# hv4layerSWV2.net
KiCad netlist of a schematic drawn in EAGLE
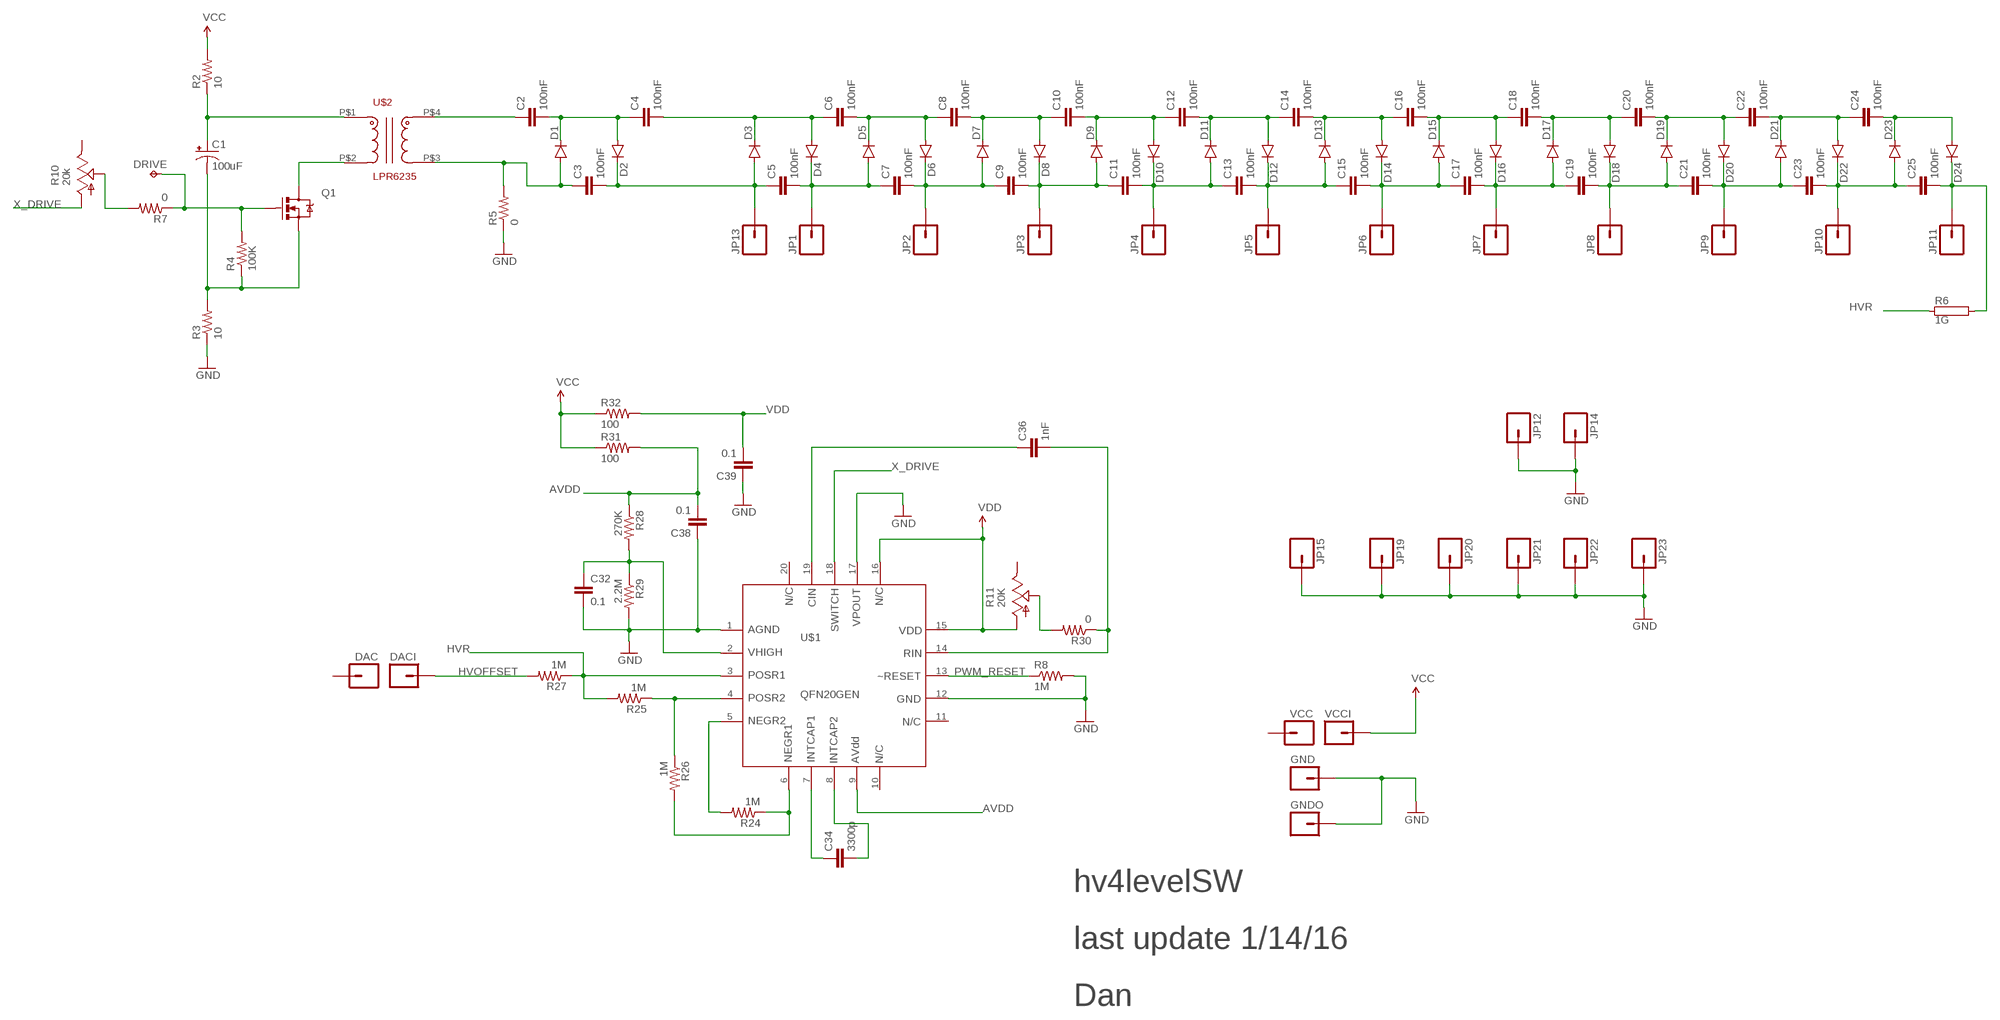
[diagram p0: schematic, sheet 1]

(export (version "E")
  (design (tool "Eeschema 10.0.6"))
  (components
    (comp (ref "C1")
      (value "100uF")
      (footprint "eagle-import:EIA6032")
      (libsource (lib "eagle-import") (part "CAP_POL6032"))
    )
    (comp (ref "C2")
      (value "100nF")
      (footprint "eagle-import:1210")
      (libsource (lib "eagle-import") (part "CAP1210"))
    )
    (comp (ref "C3")
      (value "100nF")
      (footprint "eagle-import:1210")
      (libsource (lib "eagle-import") (part "CAP1210"))
    )
    (comp (ref "C4")
      (value "100nF")
      (footprint "eagle-import:1210")
      (libsource (lib "eagle-import") (part "CAP1210"))
    )
    (comp (ref "C5")
      (value "100nF")
      (footprint "eagle-import:1210")
      (libsource (lib "eagle-import") (part "CAP1210"))
    )
    (comp (ref "C6")
      (value "100nF")
      (footprint "eagle-import:1210")
      (libsource (lib "eagle-import") (part "CAP1210"))
    )
    (comp (ref "C7")
      (value "100nF")
      (footprint "eagle-import:1210")
      (libsource (lib "eagle-import") (part "CAP1210"))
    )
    (comp (ref "C8")
      (value "100nF")
      (footprint "eagle-import:1210")
      (libsource (lib "eagle-import") (part "CAP1210"))
    )
    (comp (ref "C9")
      (value "100nF")
      (footprint "eagle-import:1210")
      (libsource (lib "eagle-import") (part "CAP1210"))
    )
    (comp (ref "C10")
      (value "100nF")
      (footprint "eagle-import:1210")
      (libsource (lib "eagle-import") (part "CAP1210"))
    )
    (comp (ref "C11")
      (value "100nF")
      (footprint "eagle-import:1210")
      (libsource (lib "eagle-import") (part "CAP1210"))
    )
    (comp (ref "C12")
      (value "100nF")
      (footprint "eagle-import:1210")
      (libsource (lib "eagle-import") (part "CAP1210"))
    )
    (comp (ref "C13")
      (value "100nF")
      (footprint "eagle-import:1210")
      (libsource (lib "eagle-import") (part "CAP1210"))
    )
    (comp (ref "C14")
      (value "100nF")
      (footprint "eagle-import:1210")
      (libsource (lib "eagle-import") (part "CAP1210"))
    )
    (comp (ref "C15")
      (value "100nF")
      (footprint "eagle-import:1210")
      (libsource (lib "eagle-import") (part "CAP1210"))
    )
    (comp (ref "C16")
      (value "100nF")
      (footprint "eagle-import:1210")
      (libsource (lib "eagle-import") (part "CAP1210"))
    )
    (comp (ref "C17")
      (value "100nF")
      (footprint "eagle-import:1210")
      (libsource (lib "eagle-import") (part "CAP1210"))
    )
    (comp (ref "C18")
      (value "100nF")
      (footprint "eagle-import:1210")
      (libsource (lib "eagle-import") (part "CAP1210"))
    )
    (comp (ref "C19")
      (value "100nF")
      (footprint "eagle-import:1210")
      (libsource (lib "eagle-import") (part "CAP1210"))
    )
    (comp (ref "C20")
      (value "100nF")
      (footprint "eagle-import:1210")
      (libsource (lib "eagle-import") (part "CAP1210"))
    )
    (comp (ref "C21")
      (value "100nF")
      (footprint "eagle-import:1210")
      (libsource (lib "eagle-import") (part "CAP1210"))
    )
    (comp (ref "C22")
      (value "100nF")
      (footprint "eagle-import:1210")
      (libsource (lib "eagle-import") (part "CAP1210"))
    )
    (comp (ref "C23")
      (value "100nF")
      (footprint "eagle-import:1210")
      (libsource (lib "eagle-import") (part "CAP1210"))
    )
    (comp (ref "C24")
      (value "100nF")
      (footprint "eagle-import:1210")
      (libsource (lib "eagle-import") (part "CAP1210"))
    )
    (comp (ref "C25")
      (value "100nF")
      (footprint "eagle-import:1210")
      (libsource (lib "eagle-import") (part "CAP1210"))
    )
    (comp (ref "C32")
      (value "0.1")
      (footprint "eagle-import:0805")
      (libsource (lib "eagle-import") (part "22UF-6.3V-20%(0805)"))
    )
    (comp (ref "C34")
      (value "3300p")
      (footprint "eagle-import:0805")
      (libsource (lib "eagle-import") (part "22UF-6.3V-20%(0805)"))
    )
    (comp (ref "C36")
      (value "1nF")
      (footprint "eagle-import:0805")
      (libsource (lib "eagle-import") (part "22UF-6.3V-20%(0805)"))
    )
    (comp (ref "C38")
      (value "0.1")
      (footprint "eagle-import:0805")
      (libsource (lib "eagle-import") (part "22UF-6.3V-20%(0805)"))
    )
    (comp (ref "C39")
      (value "0.1")
      (footprint "eagle-import:0805")
      (libsource (lib "eagle-import") (part "22UF-6.3V-20%(0805)"))
    )
    (comp (ref "D1")
      (value "DIODESOT23")
      (footprint "eagle-import:SOT23-3")
      (libsource (lib "eagle-import") (part "DIODESOT23"))
    )
    (comp (ref "D2")
      (value "DIODESOT23")
      (footprint "eagle-import:SOT23-3")
      (libsource (lib "eagle-import") (part "DIODESOT23"))
    )
    (comp (ref "D3")
      (value "DIODESOT23")
      (footprint "eagle-import:SOT23-3")
      (libsource (lib "eagle-import") (part "DIODESOT23"))
    )
    (comp (ref "D4")
      (value "DIODESOT23")
      (footprint "eagle-import:SOT23-3")
      (libsource (lib "eagle-import") (part "DIODESOT23"))
    )
    (comp (ref "D5")
      (value "DIODESOT23")
      (footprint "eagle-import:SOT23-3")
      (libsource (lib "eagle-import") (part "DIODESOT23"))
    )
    (comp (ref "D6")
      (value "DIODESOT23")
      (footprint "eagle-import:SOT23-3")
      (libsource (lib "eagle-import") (part "DIODESOT23"))
    )
    (comp (ref "D7")
      (value "DIODESOT23")
      (footprint "eagle-import:SOT23-3")
      (libsource (lib "eagle-import") (part "DIODESOT23"))
    )
    (comp (ref "D8")
      (value "DIODESOT23")
      (footprint "eagle-import:SOT23-3")
      (libsource (lib "eagle-import") (part "DIODESOT23"))
    )
    (comp (ref "D9")
      (value "DIODESOT23")
      (footprint "eagle-import:SOT23-3")
      (libsource (lib "eagle-import") (part "DIODESOT23"))
    )
    (comp (ref "D10")
      (value "DIODESOT23")
      (footprint "eagle-import:SOT23-3")
      (libsource (lib "eagle-import") (part "DIODESOT23"))
    )
    (comp (ref "D11")
      (value "DIODESOT23")
      (footprint "eagle-import:SOT23-3")
      (libsource (lib "eagle-import") (part "DIODESOT23"))
    )
    (comp (ref "D12")
      (value "DIODESOT23")
      (footprint "eagle-import:SOT23-3")
      (libsource (lib "eagle-import") (part "DIODESOT23"))
    )
    (comp (ref "D13")
      (value "DIODESOT23")
      (footprint "eagle-import:SOT23-3")
      (libsource (lib "eagle-import") (part "DIODESOT23"))
    )
    (comp (ref "D14")
      (value "DIODESOT23")
      (footprint "eagle-import:SOT23-3")
      (libsource (lib "eagle-import") (part "DIODESOT23"))
    )
    (comp (ref "D15")
      (value "DIODESOT23")
      (footprint "eagle-import:SOT23-3")
      (libsource (lib "eagle-import") (part "DIODESOT23"))
    )
    (comp (ref "D16")
      (value "DIODESOT23")
      (footprint "eagle-import:SOT23-3")
      (libsource (lib "eagle-import") (part "DIODESOT23"))
    )
    (comp (ref "D17")
      (value "DIODESOT23")
      (footprint "eagle-import:SOT23-3")
      (libsource (lib "eagle-import") (part "DIODESOT23"))
    )
    (comp (ref "D18")
      (value "DIODESOT23")
      (footprint "eagle-import:SOT23-3")
      (libsource (lib "eagle-import") (part "DIODESOT23"))
    )
    (comp (ref "D19")
      (value "DIODESOT23")
      (footprint "eagle-import:SOT23-3")
      (libsource (lib "eagle-import") (part "DIODESOT23"))
    )
    (comp (ref "D20")
      (value "DIODESOT23")
      (footprint "eagle-import:SOT23-3")
      (libsource (lib "eagle-import") (part "DIODESOT23"))
    )
    (comp (ref "D21")
      (value "DIODESOT23")
      (footprint "eagle-import:SOT23-3")
      (libsource (lib "eagle-import") (part "DIODESOT23"))
    )
    (comp (ref "D22")
      (value "DIODESOT23")
      (footprint "eagle-import:SOT23-3")
      (libsource (lib "eagle-import") (part "DIODESOT23"))
    )
    (comp (ref "D23")
      (value "DIODESOT23")
      (footprint "eagle-import:SOT23-3")
      (libsource (lib "eagle-import") (part "DIODESOT23"))
    )
    (comp (ref "D24")
      (value "DIODESOT23")
      (footprint "eagle-import:SOT23-3")
      (libsource (lib "eagle-import") (part "DIODESOT23"))
    )
    (comp (ref "DAC")
      (value "M01PTH")
      (footprint "eagle-import:1X01")
      (libsource (lib "eagle-import") (part "M01PTH"))
    )
    (comp (ref "DACI")
      (value "M01PTH")
      (footprint "eagle-import:1X01")
      (libsource (lib "eagle-import") (part "M01PTH"))
    )
    (comp (ref "DRIVE")
      (value "TPTP20R")
      (footprint "eagle-import:TP20R")
      (libsource (lib "eagle-import") (part "TPTP20R"))
    )
    (comp (ref "GND")
      (value "M01PTH")
      (footprint "eagle-import:1X01")
      (libsource (lib "eagle-import") (part "M01PTH"))
    )
    (comp (ref "GNDO")
      (value "M01PTH")
      (footprint "eagle-import:1X01")
      (libsource (lib "eagle-import") (part "M01PTH"))
    )
    (comp (ref "JP1")
      (value "M01PTH")
      (footprint "eagle-import:1X01")
      (libsource (lib "eagle-import") (part "M01PTH"))
    )
    (comp (ref "JP2")
      (value "M01PTH")
      (footprint "eagle-import:1X01")
      (libsource (lib "eagle-import") (part "M01PTH"))
    )
    (comp (ref "JP3")
      (value "M01PTH")
      (footprint "eagle-import:1X01")
      (libsource (lib "eagle-import") (part "M01PTH"))
    )
    (comp (ref "JP4")
      (value "M01PTH")
      (footprint "eagle-import:1X01")
      (libsource (lib "eagle-import") (part "M01PTH"))
    )
    (comp (ref "JP5")
      (value "M01PTH")
      (footprint "eagle-import:1X01")
      (libsource (lib "eagle-import") (part "M01PTH"))
    )
    (comp (ref "JP6")
      (value "M01PTH")
      (footprint "eagle-import:1X01")
      (libsource (lib "eagle-import") (part "M01PTH"))
    )
    (comp (ref "JP7")
      (value "M01PTH")
      (footprint "eagle-import:1X01")
      (libsource (lib "eagle-import") (part "M01PTH"))
    )
    (comp (ref "JP8")
      (value "M01PTH")
      (footprint "eagle-import:1X01")
      (libsource (lib "eagle-import") (part "M01PTH"))
    )
    (comp (ref "JP9")
      (value "M01PTH")
      (footprint "eagle-import:1X01")
      (libsource (lib "eagle-import") (part "M01PTH"))
    )
    (comp (ref "JP10")
      (value "M01PTH")
      (footprint "eagle-import:1X01")
      (libsource (lib "eagle-import") (part "M01PTH"))
    )
    (comp (ref "JP11")
      (value "M01PTH")
      (footprint "eagle-import:1X01")
      (libsource (lib "eagle-import") (part "M01PTH"))
    )
    (comp (ref "JP12")
      (value "M01PTH")
      (footprint "eagle-import:1X01")
      (libsource (lib "eagle-import") (part "M01PTH"))
    )
    (comp (ref "JP13")
      (value "M01PTH")
      (footprint "eagle-import:1X01")
      (libsource (lib "eagle-import") (part "M01PTH"))
    )
    (comp (ref "JP14")
      (value "M01PTH")
      (footprint "eagle-import:1X01")
      (libsource (lib "eagle-import") (part "M01PTH"))
    )
    (comp (ref "JP15")
      (value "M01PTH")
      (footprint "eagle-import:1X01")
      (libsource (lib "eagle-import") (part "M01PTH"))
    )
    (comp (ref "JP19")
      (value "M01PTH")
      (footprint "eagle-import:1X01")
      (libsource (lib "eagle-import") (part "M01PTH"))
    )
    (comp (ref "JP20")
      (value "M01PTH")
      (footprint "eagle-import:1X01")
      (libsource (lib "eagle-import") (part "M01PTH"))
    )
    (comp (ref "JP21")
      (value "M01PTH")
      (footprint "eagle-import:1X01")
      (libsource (lib "eagle-import") (part "M01PTH"))
    )
    (comp (ref "JP22")
      (value "M01PTH")
      (footprint "eagle-import:1X01")
      (libsource (lib "eagle-import") (part "M01PTH"))
    )
    (comp (ref "JP23")
      (value "M01PTH")
      (footprint "eagle-import:1X01")
      (libsource (lib "eagle-import") (part "M01PTH"))
    )
    (comp (ref "Q1")
      (value "MOSFET-NCHANNELAO3404A")
      (footprint "eagle-import:SOT23-3")
      (libsource (lib "eagle-import") (part "MOSFET-NCHANNELAO3404A"))
    )
    (comp (ref "R2")
      (value "10")
      (footprint "eagle-import:R2512")
      (libsource (lib "eagle-import") (part "SparkFun-Resistors_RESISTOR2512"))
    )
    (comp (ref "R3")
      (value "10")
      (footprint "eagle-import:R2512")
      (libsource (lib "eagle-import") (part "SparkFun-Resistors_RESISTOR2512"))
    )
    (comp (ref "R4")
      (value "100K")
      (footprint "eagle-import:0805")
      (libsource (lib "eagle-import") (part "RESISTOR0805-RES"))
    )
    (comp (ref "R5")
      (value "0")
      (footprint "eagle-import:0805")
      (libsource (lib "eagle-import") (part "RESISTOR0805-RES"))
    )
    (comp (ref "R6")
      (value "1G")
      (footprint "eagle-import:CA4090")
      (libsource (lib "eagle-import") (part "RCA4090"))
    )
    (comp (ref "R7")
      (value "0")
      (footprint "eagle-import:0805")
      (libsource (lib "eagle-import") (part "RESISTOR0805-RES"))
    )
    (comp (ref "R8")
      (value "1M")
      (footprint "eagle-import:0805")
      (libsource (lib "eagle-import") (part "RESISTOR0805-RES"))
    )
    (comp (ref "R10")
      (value "20k")
      (footprint "eagle-import:3223W")
      (libsource (lib "eagle-import") (part "TRIM_US-3223W"))
    )
    (comp (ref "R11")
      (value "20K")
      (footprint "eagle-import:3223W")
      (libsource (lib "eagle-import") (part "TRIM_US-3223W"))
    )
    (comp (ref "R24")
      (value "1M")
      (footprint "eagle-import:0805")
      (libsource (lib "eagle-import") (part "RESISTOR0805-RES"))
    )
    (comp (ref "R25")
      (value "1M")
      (footprint "eagle-import:0805")
      (libsource (lib "eagle-import") (part "RESISTOR0805-RES"))
    )
    (comp (ref "R26")
      (value "1M")
      (footprint "eagle-import:0805")
      (libsource (lib "eagle-import") (part "RESISTOR0805-RES"))
    )
    (comp (ref "R27")
      (value "1M")
      (footprint "eagle-import:0805")
      (libsource (lib "eagle-import") (part "RESISTOR0805-RES"))
    )
    (comp (ref "R28")
      (value "270K")
      (footprint "eagle-import:0805")
      (libsource (lib "eagle-import") (part "RESISTOR0805-RES"))
    )
    (comp (ref "R29")
      (value "2.2M")
      (footprint "eagle-import:0805")
      (libsource (lib "eagle-import") (part "RESISTOR0805-RES"))
    )
    (comp (ref "R30")
      (value "0")
      (footprint "eagle-import:0805")
      (libsource (lib "eagle-import") (part "RESISTOR0805-RES"))
    )
    (comp (ref "R31")
      (value "100")
      (footprint "eagle-import:0805")
      (libsource (lib "eagle-import") (part "RESISTOR0805-RES"))
    )
    (comp (ref "R32")
      (value "100")
      (footprint "eagle-import:0805")
      (libsource (lib "eagle-import") (part "RESISTOR0805-RES"))
    )
    (comp (ref "U$1")
      (value "QFN20GEN")
      (footprint "eagle-import:QFN20")
      (libsource (lib "eagle-import") (part "QFN20GEN"))
    )
    (comp (ref "U$2")
      (value "LPR6235")
      (footprint "eagle-import:LPR6235")
      (libsource (lib "eagle-import") (part "LPR6235"))
    )
    (comp (ref "VCC")
      (value "M01PTH")
      (footprint "eagle-import:1X01")
      (libsource (lib "eagle-import") (part "M01PTH"))
    )
    (comp (ref "VCCI")
      (value "M01PTH")
      (footprint "eagle-import:1X01")
      (libsource (lib "eagle-import") (part "M01PTH"))
    )
  )
  (nets
    (net (code "1") (name "/AVDD") (class "Default")
      (node (ref "C38") (pin "2") (pinfunction "2_2") (pintype "passive"))
      (node (ref "R28") (pin "1") (pinfunction "1_1") (pintype "passive"))
      (node (ref "R31") (pin "2") (pinfunction "2_2") (pintype "passive"))
      (node (ref "U$1") (pin "9") (pinfunction "P$9_9") (pintype "bidirectional"))
    )
    (net (code "2") (name "/HVOFFSET") (class "Default")
      (node (ref "DACI") (pin "1") (pinfunction "1_1") (pintype "passive"))
      (node (ref "R27") (pin "2") (pinfunction "2_2") (pintype "passive"))
    )
    (net (code "3") (name "/HVR") (class "Default")
      (node (ref "R25") (pin "2") (pinfunction "2_2") (pintype "passive"))
      (node (ref "R27") (pin "1") (pinfunction "1_1") (pintype "passive"))
      (node (ref "R6") (pin "1") (pinfunction "1_1") (pintype "passive"))
      (node (ref "U$1") (pin "3") (pinfunction "P$3_3") (pintype "bidirectional"))
    )
    (net (code "4") (name "/PWM_RESET") (class "Default")
      (node (ref "R8") (pin "1") (pinfunction "1_1") (pintype "passive"))
      (node (ref "U$1") (pin "13") (pinfunction "P$13_13") (pintype "bidirectional"))
    )
    (net (code "5") (name "/X_DRIVE") (class "Default")
      (node (ref "R10") (pin "1") (pinfunction "A_1") (pintype "passive"))
      (node (ref "U$1") (pin "18") (pinfunction "P$18_18") (pintype "bidirectional"))
    )
    (net (code "6") (name "GND") (class "Default")
      (node (ref "C32") (pin "2") (pinfunction "2_2") (pintype "passive"))
      (node (ref "C38") (pin "1") (pinfunction "1_1") (pintype "passive"))
      (node (ref "C39") (pin "1") (pinfunction "1_1") (pintype "passive"))
      (node (ref "GND") (pin "1") (pinfunction "1_1") (pintype "passive"))
      (node (ref "GNDO") (pin "1") (pinfunction "1_1") (pintype "passive"))
      (node (ref "JP12") (pin "1") (pinfunction "1_1") (pintype "passive"))
      (node (ref "JP14") (pin "1") (pinfunction "1_1") (pintype "passive"))
      (node (ref "JP15") (pin "1") (pinfunction "1_1") (pintype "passive"))
      (node (ref "JP19") (pin "1") (pinfunction "1_1") (pintype "passive"))
      (node (ref "JP20") (pin "1") (pinfunction "1_1") (pintype "passive"))
      (node (ref "JP21") (pin "1") (pinfunction "1_1") (pintype "passive"))
      (node (ref "JP22") (pin "1") (pinfunction "1_1") (pintype "passive"))
      (node (ref "JP23") (pin "1") (pinfunction "1_1") (pintype "passive"))
      (node (ref "R29") (pin "2") (pinfunction "2_2") (pintype "passive"))
      (node (ref "R3") (pin "1") (pinfunction "1_1") (pintype "passive"))
      (node (ref "R5") (pin "1") (pinfunction "1_1") (pintype "passive"))
      (node (ref "R8") (pin "2") (pinfunction "2_2") (pintype "passive"))
      (node (ref "U$1") (pin "1") (pinfunction "P$1_1") (pintype "bidirectional"))
      (node (ref "U$1") (pin "12") (pinfunction "P$12_12") (pintype "bidirectional"))
      (node (ref "U$1") (pin "17") (pinfunction "P$17_17") (pintype "bidirectional"))
    )
    (net (code "7") (name "Net-(C1-+)") (class "Default")
      (node (ref "C1") (pin "P$1") (pinfunction "+_P$1") (pintype "passive"))
      (node (ref "R2") (pin "1") (pinfunction "1_1") (pintype "passive"))
      (node (ref "U$2") (pin "P$1") (pinfunction "1_P$1") (pintype "passive"))
    )
    (net (code "8") (name "Net-(C1--)") (class "Default")
      (node (ref "C1") (pin "P$2") (pinfunction "-_P$2") (pintype "passive"))
      (node (ref "Q1") (pin "2") (pinfunction "S_2") (pintype "passive"))
      (node (ref "R3") (pin "2") (pinfunction "2_2") (pintype "passive"))
      (node (ref "R4") (pin "1") (pinfunction "1_1") (pintype "passive"))
    )
    (net (code "9") (name "Net-(D1-A)") (class "Default")
      (node (ref "C3") (pin "1") (pinfunction "1_1") (pintype "passive"))
      (node (ref "D1") (pin "1") (pinfunction "A_1") (pintype "passive"))
      (node (ref "R5") (pin "2") (pinfunction "2_2") (pintype "passive"))
      (node (ref "U$2") (pin "P$3") (pinfunction "5_P$3") (pintype "passive"))
    )
    (net (code "10") (name "Net-(D1-C)") (class "Default")
      (node (ref "C2") (pin "2") (pinfunction "2_2") (pintype "passive"))
      (node (ref "C4") (pin "1") (pinfunction "1_1") (pintype "passive"))
      (node (ref "D1") (pin "3") (pinfunction "C_3") (pintype "passive"))
      (node (ref "D2") (pin "1") (pinfunction "A_1") (pintype "passive"))
    )
    (net (code "11") (name "Net-(D2-C)") (class "Default")
      (node (ref "C3") (pin "2") (pinfunction "2_2") (pintype "passive"))
      (node (ref "C5") (pin "1") (pinfunction "1_1") (pintype "passive"))
      (node (ref "D2") (pin "3") (pinfunction "C_3") (pintype "passive"))
      (node (ref "D3") (pin "1") (pinfunction "A_1") (pintype "passive"))
      (node (ref "JP13") (pin "1") (pinfunction "1_1") (pintype "passive"))
    )
    (net (code "12") (name "Net-(D3-C)") (class "Default")
      (node (ref "C4") (pin "2") (pinfunction "2_2") (pintype "passive"))
      (node (ref "C6") (pin "1") (pinfunction "1_1") (pintype "passive"))
      (node (ref "D3") (pin "3") (pinfunction "C_3") (pintype "passive"))
      (node (ref "D4") (pin "1") (pinfunction "A_1") (pintype "passive"))
    )
    (net (code "13") (name "Net-(D4-C)") (class "Default")
      (node (ref "C5") (pin "2") (pinfunction "2_2") (pintype "passive"))
      (node (ref "C7") (pin "1") (pinfunction "1_1") (pintype "passive"))
      (node (ref "D4") (pin "3") (pinfunction "C_3") (pintype "passive"))
      (node (ref "D5") (pin "1") (pinfunction "A_1") (pintype "passive"))
      (node (ref "JP1") (pin "1") (pinfunction "1_1") (pintype "passive"))
    )
    (net (code "14") (name "Net-(D5-C)") (class "Default")
      (node (ref "C6") (pin "2") (pinfunction "2_2") (pintype "passive"))
      (node (ref "C8") (pin "1") (pinfunction "1_1") (pintype "passive"))
      (node (ref "D5") (pin "3") (pinfunction "C_3") (pintype "passive"))
      (node (ref "D6") (pin "1") (pinfunction "A_1") (pintype "passive"))
    )
    (net (code "15") (name "Net-(D6-C)") (class "Default")
      (node (ref "C7") (pin "2") (pinfunction "2_2") (pintype "passive"))
      (node (ref "C9") (pin "1") (pinfunction "1_1") (pintype "passive"))
      (node (ref "D6") (pin "3") (pinfunction "C_3") (pintype "passive"))
      (node (ref "D7") (pin "1") (pinfunction "A_1") (pintype "passive"))
      (node (ref "JP2") (pin "1") (pinfunction "1_1") (pintype "passive"))
    )
    (net (code "16") (name "Net-(D7-C)") (class "Default")
      (node (ref "C10") (pin "1") (pinfunction "1_1") (pintype "passive"))
      (node (ref "C8") (pin "2") (pinfunction "2_2") (pintype "passive"))
      (node (ref "D7") (pin "3") (pinfunction "C_3") (pintype "passive"))
      (node (ref "D8") (pin "1") (pinfunction "A_1") (pintype "passive"))
    )
    (net (code "17") (name "Net-(D8-C)") (class "Default")
      (node (ref "C11") (pin "1") (pinfunction "1_1") (pintype "passive"))
      (node (ref "C9") (pin "2") (pinfunction "2_2") (pintype "passive"))
      (node (ref "D8") (pin "3") (pinfunction "C_3") (pintype "passive"))
      (node (ref "D9") (pin "1") (pinfunction "A_1") (pintype "passive"))
      (node (ref "JP3") (pin "1") (pinfunction "1_1") (pintype "passive"))
    )
    (net (code "18") (name "Net-(D10-A)") (class "Default")
      (node (ref "C10") (pin "2") (pinfunction "2_2") (pintype "passive"))
      (node (ref "C12") (pin "1") (pinfunction "1_1") (pintype "passive"))
      (node (ref "D10") (pin "1") (pinfunction "A_1") (pintype "passive"))
      (node (ref "D9") (pin "3") (pinfunction "C_3") (pintype "passive"))
    )
    (net (code "19") (name "Net-(D10-C)") (class "Default")
      (node (ref "C11") (pin "2") (pinfunction "2_2") (pintype "passive"))
      (node (ref "C13") (pin "1") (pinfunction "1_1") (pintype "passive"))
      (node (ref "D10") (pin "3") (pinfunction "C_3") (pintype "passive"))
      (node (ref "D11") (pin "1") (pinfunction "A_1") (pintype "passive"))
      (node (ref "JP4") (pin "1") (pinfunction "1_1") (pintype "passive"))
    )
    (net (code "20") (name "Net-(D11-C)") (class "Default")
      (node (ref "C12") (pin "2") (pinfunction "2_2") (pintype "passive"))
      (node (ref "C14") (pin "1") (pinfunction "1_1") (pintype "passive"))
      (node (ref "D11") (pin "3") (pinfunction "C_3") (pintype "passive"))
      (node (ref "D12") (pin "1") (pinfunction "A_1") (pintype "passive"))
    )
    (net (code "21") (name "Net-(D12-C)") (class "Default")
      (node (ref "C13") (pin "2") (pinfunction "2_2") (pintype "passive"))
      (node (ref "C15") (pin "1") (pinfunction "1_1") (pintype "passive"))
      (node (ref "D12") (pin "3") (pinfunction "C_3") (pintype "passive"))
      (node (ref "D13") (pin "1") (pinfunction "A_1") (pintype "passive"))
      (node (ref "JP5") (pin "1") (pinfunction "1_1") (pintype "passive"))
    )
    (net (code "22") (name "Net-(D13-C)") (class "Default")
      (node (ref "C14") (pin "2") (pinfunction "2_2") (pintype "passive"))
      (node (ref "C16") (pin "1") (pinfunction "1_1") (pintype "passive"))
      (node (ref "D13") (pin "3") (pinfunction "C_3") (pintype "passive"))
      (node (ref "D14") (pin "1") (pinfunction "A_1") (pintype "passive"))
    )
    (net (code "23") (name "Net-(D14-C)") (class "Default")
      (node (ref "C15") (pin "2") (pinfunction "2_2") (pintype "passive"))
      (node (ref "C17") (pin "1") (pinfunction "1_1") (pintype "passive"))
      (node (ref "D14") (pin "3") (pinfunction "C_3") (pintype "passive"))
      (node (ref "D15") (pin "1") (pinfunction "A_1") (pintype "passive"))
      (node (ref "JP6") (pin "1") (pinfunction "1_1") (pintype "passive"))
    )
    (net (code "24") (name "Net-(D15-C)") (class "Default")
      (node (ref "C16") (pin "2") (pinfunction "2_2") (pintype "passive"))
      (node (ref "C18") (pin "1") (pinfunction "1_1") (pintype "passive"))
      (node (ref "D15") (pin "3") (pinfunction "C_3") (pintype "passive"))
      (node (ref "D16") (pin "1") (pinfunction "A_1") (pintype "passive"))
    )
    (net (code "25") (name "Net-(D16-C)") (class "Default")
      (node (ref "C17") (pin "2") (pinfunction "2_2") (pintype "passive"))
      (node (ref "C19") (pin "1") (pinfunction "1_1") (pintype "passive"))
      (node (ref "D16") (pin "3") (pinfunction "C_3") (pintype "passive"))
      (node (ref "D17") (pin "1") (pinfunction "A_1") (pintype "passive"))
      (node (ref "JP7") (pin "1") (pinfunction "1_1") (pintype "passive"))
    )
    (net (code "26") (name "Net-(D17-C)") (class "Default")
      (node (ref "C18") (pin "2") (pinfunction "2_2") (pintype "passive"))
      (node (ref "C20") (pin "1") (pinfunction "1_1") (pintype "passive"))
      (node (ref "D17") (pin "3") (pinfunction "C_3") (pintype "passive"))
      (node (ref "D18") (pin "1") (pinfunction "A_1") (pintype "passive"))
    )
    (net (code "27") (name "Net-(D18-C)") (class "Default")
      (node (ref "C19") (pin "2") (pinfunction "2_2") (pintype "passive"))
      (node (ref "C21") (pin "1") (pinfunction "1_1") (pintype "passive"))
      (node (ref "D18") (pin "3") (pinfunction "C_3") (pintype "passive"))
      (node (ref "D19") (pin "1") (pinfunction "A_1") (pintype "passive"))
      (node (ref "JP8") (pin "1") (pinfunction "1_1") (pintype "passive"))
    )
    (net (code "28") (name "Net-(D19-C)") (class "Default")
      (node (ref "C20") (pin "2") (pinfunction "2_2") (pintype "passive"))
      (node (ref "C22") (pin "1") (pinfunction "1_1") (pintype "passive"))
      (node (ref "D19") (pin "3") (pinfunction "C_3") (pintype "passive"))
      (node (ref "D20") (pin "1") (pinfunction "A_1") (pintype "passive"))
    )
    (net (code "29") (name "Net-(D20-C)") (class "Default")
      (node (ref "C21") (pin "2") (pinfunction "2_2") (pintype "passive"))
      (node (ref "C23") (pin "1") (pinfunction "1_1") (pintype "passive"))
      (node (ref "D20") (pin "3") (pinfunction "C_3") (pintype "passive"))
      (node (ref "D21") (pin "1") (pinfunction "A_1") (pintype "passive"))
      (node (ref "JP9") (pin "1") (pinfunction "1_1") (pintype "passive"))
    )
    (net (code "30") (name "Net-(D21-C)") (class "Default")
      (node (ref "C22") (pin "2") (pinfunction "2_2") (pintype "passive"))
      (node (ref "C24") (pin "1") (pinfunction "1_1") (pintype "passive"))
      (node (ref "D21") (pin "3") (pinfunction "C_3") (pintype "passive"))
      (node (ref "D22") (pin "1") (pinfunction "A_1") (pintype "passive"))
    )
    (net (code "31") (name "Net-(D22-C)") (class "Default")
      (node (ref "C23") (pin "2") (pinfunction "2_2") (pintype "passive"))
      (node (ref "C25") (pin "1") (pinfunction "1_1") (pintype "passive"))
      (node (ref "D22") (pin "3") (pinfunction "C_3") (pintype "passive"))
      (node (ref "D23") (pin "1") (pinfunction "A_1") (pintype "passive"))
      (node (ref "JP10") (pin "1") (pinfunction "1_1") (pintype "passive"))
    )
    (net (code "32") (name "Net-(D23-C)") (class "Default")
      (node (ref "C24") (pin "2") (pinfunction "2_2") (pintype "passive"))
      (node (ref "D23") (pin "3") (pinfunction "C_3") (pintype "passive"))
      (node (ref "D24") (pin "1") (pinfunction "A_1") (pintype "passive"))
    )
    (net (code "33") (name "Net-(D24-C)") (class "Default")
      (node (ref "C25") (pin "2") (pinfunction "2_2") (pintype "passive"))
      (node (ref "D24") (pin "3") (pinfunction "C_3") (pintype "passive"))
      (node (ref "JP11") (pin "1") (pinfunction "1_1") (pintype "passive"))
      (node (ref "R6") (pin "2") (pinfunction "2_2") (pintype "passive"))
    )
    (net (code "34") (name "Net-(Q1-D)") (class "Default")
      (node (ref "Q1") (pin "3") (pinfunction "D_3") (pintype "passive"))
      (node (ref "U$2") (pin "P$2") (pinfunction "2_P$2") (pintype "passive"))
    )
    (net (code "35") (name "Net-(Q1-G)") (class "Default")
      (node (ref "DRIVE") (pin "TP") (pinfunction "TP_TP") (pintype "input"))
      (node (ref "Q1") (pin "1") (pinfunction "G_1") (pintype "passive"))
      (node (ref "R4") (pin "2") (pinfunction "2_2") (pintype "passive"))
      (node (ref "R7") (pin "1") (pinfunction "1_1") (pintype "passive"))
    )
    (net (code "36") (name "Net-(R10-S)") (class "Default")
      (node (ref "R10") (pin "2") (pinfunction "S_2") (pintype "passive"))
      (node (ref "R7") (pin "2") (pinfunction "2_2") (pintype "passive"))
    )
    (net (code "37") (name "Net-(R11-S)") (class "Default")
      (node (ref "R11") (pin "2") (pinfunction "S_2") (pintype "passive"))
      (node (ref "R30") (pin "2") (pinfunction "2_2") (pintype "passive"))
    )
    (net (code "38") (name "Net-(U$1-P$2)") (class "Default")
      (node (ref "C32") (pin "1") (pinfunction "1_1") (pintype "passive"))
      (node (ref "R28") (pin "2") (pinfunction "2_2") (pintype "passive"))
      (node (ref "R29") (pin "1") (pinfunction "1_1") (pintype "passive"))
      (node (ref "U$1") (pin "2") (pinfunction "P$2_2") (pintype "bidirectional"))
    )
    (net (code "39") (name "Net-(U$1-P$4)") (class "Default")
      (node (ref "R25") (pin "1") (pinfunction "1_1") (pintype "passive"))
      (node (ref "R26") (pin "1") (pinfunction "1_1") (pintype "passive"))
      (node (ref "U$1") (pin "4") (pinfunction "P$4_4") (pintype "bidirectional"))
    )
    (net (code "40") (name "Net-(U$1-P$5)") (class "Default")
      (node (ref "R24") (pin "2") (pinfunction "2_2") (pintype "passive"))
      (node (ref "U$1") (pin "5") (pinfunction "P$5_5") (pintype "bidirectional"))
    )
    (net (code "41") (name "Net-(U$1-P$6)") (class "Default")
      (node (ref "R24") (pin "1") (pinfunction "1_1") (pintype "passive"))
      (node (ref "R26") (pin "2") (pinfunction "2_2") (pintype "passive"))
      (node (ref "U$1") (pin "6") (pinfunction "P$6_6") (pintype "bidirectional"))
    )
    (net (code "42") (name "Net-(U$1-P$7)") (class "Default")
      (node (ref "C34") (pin "1") (pinfunction "1_1") (pintype "passive"))
      (node (ref "U$1") (pin "7") (pinfunction "P$7_7") (pintype "bidirectional"))
    )
    (net (code "43") (name "Net-(U$1-P$8)") (class "Default")
      (node (ref "C34") (pin "2") (pinfunction "2_2") (pintype "passive"))
      (node (ref "U$1") (pin "8") (pinfunction "P$8_8") (pintype "bidirectional"))
    )
    (net (code "44") (name "Net-(U$1-P$14)") (class "Default")
      (node (ref "C36") (pin "2") (pinfunction "2_2") (pintype "passive"))
      (node (ref "R30") (pin "1") (pinfunction "1_1") (pintype "passive"))
      (node (ref "U$1") (pin "14") (pinfunction "P$14_14") (pintype "bidirectional"))
    )
    (net (code "45") (name "Net-(U$1-P$19)") (class "Default")
      (node (ref "C36") (pin "1") (pinfunction "1_1") (pintype "passive"))
      (node (ref "U$1") (pin "19") (pinfunction "P$19_19") (pintype "bidirectional"))
    )
    (net (code "46") (name "Net-(U$2-4)") (class "Default")
      (node (ref "C2") (pin "1") (pinfunction "1_1") (pintype "passive"))
      (node (ref "U$2") (pin "P$4") (pinfunction "4_P$4") (pintype "passive"))
    )
    (net (code "47") (name "VCC") (class "Default")
      (node (ref "R2") (pin "2") (pinfunction "2_2") (pintype "passive"))
      (node (ref "R31") (pin "1") (pinfunction "1_1") (pintype "passive"))
      (node (ref "R32") (pin "1") (pinfunction "1_1") (pintype "passive"))
      (node (ref "VCCI") (pin "1") (pinfunction "1_1") (pintype "passive"))
    )
    (net (code "48") (name "VDD") (class "Default")
      (node (ref "C39") (pin "2") (pinfunction "2_2") (pintype "passive"))
      (node (ref "R11") (pin "1") (pinfunction "A_1") (pintype "passive"))
      (node (ref "R32") (pin "2") (pinfunction "2_2") (pintype "passive"))
      (node (ref "U$1") (pin "15") (pinfunction "P$15_15") (pintype "bidirectional"))
      (node (ref "U$1") (pin "16") (pinfunction "P$16_16") (pintype "bidirectional"))
    )
    (net (code "49") (name "unconnected-(DAC-Pad1)") (class "Default")
      (node (ref "DAC") (pin "1") (pinfunction "1_1") (pintype "passive"))
    )
    (net (code "50") (name "unconnected-(R10-E-Pad3)") (class "Default")
      (node (ref "R10") (pin "3") (pinfunction "E_3") (pintype "passive"))
    )
    (net (code "51") (name "unconnected-(R11-E-Pad3)") (class "Default")
      (node (ref "R11") (pin "3") (pinfunction "E_3") (pintype "passive"))
    )
    (net (code "52") (name "unconnected-(U$1-P$10-Pad10)") (class "Default")
      (node (ref "U$1") (pin "10") (pinfunction "P$10_10") (pintype "bidirectional"))
    )
    (net (code "53") (name "unconnected-(U$1-P$11-Pad11)") (class "Default")
      (node (ref "U$1") (pin "11") (pinfunction "P$11_11") (pintype "bidirectional"))
    )
    (net (code "54") (name "unconnected-(U$1-P$20-Pad20)") (class "Default")
      (node (ref "U$1") (pin "20") (pinfunction "P$20_20") (pintype "bidirectional"))
    )
    (net (code "55") (name "unconnected-(VCC-Pad1)") (class "Default")
      (node (ref "VCC") (pin "1") (pinfunction "1_1") (pintype "passive"))
    )
  )
)
